# 9_Fans_Control.net
KiCad netlist of a schematic drawn in Altium Designer
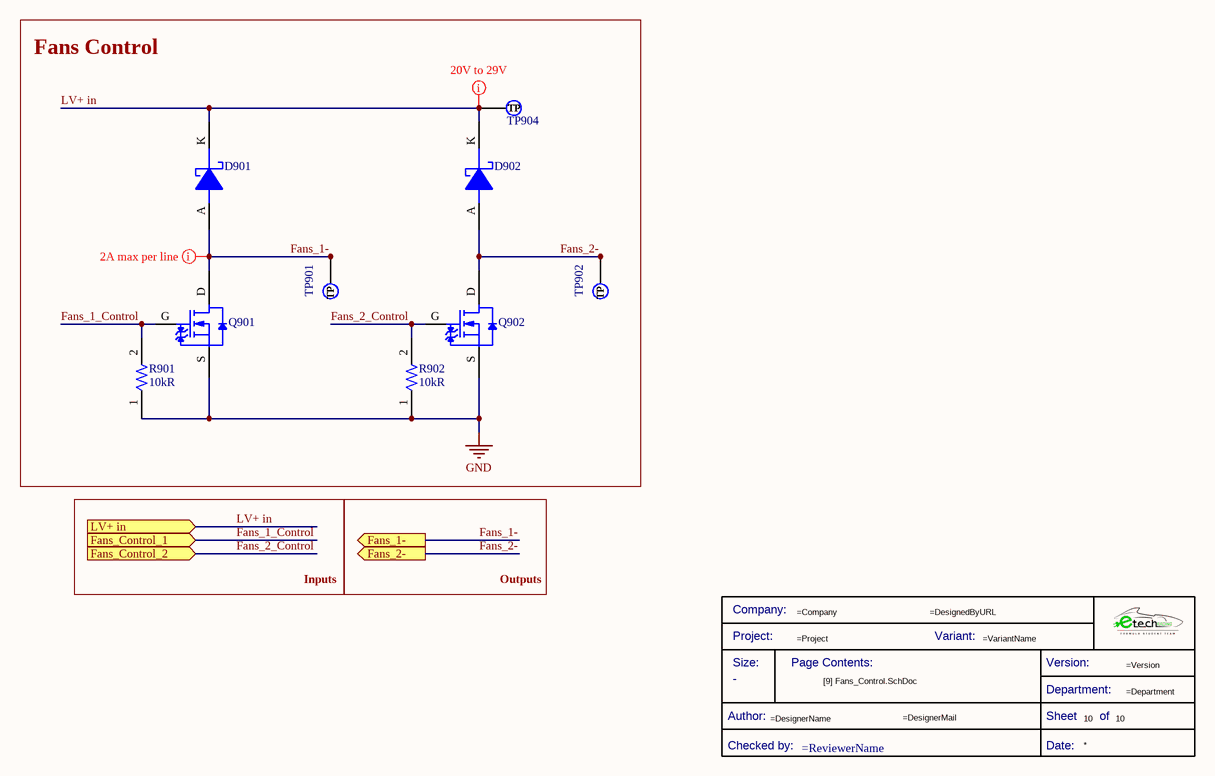
[diagram p0: [9] Fans_Control.SchDoc]

(export (version "E")
  (design (tool "Eeschema 10.0.6"))
  (components
    (comp (ref "*")
      (value "Title Block_template")
      (description "Standard Title Block")
      (fields (field (name "SIZE") "-"))
      (libsource (lib "e-Tech_Racing") (part "Title Block_template"))
    )
    (comp (ref "D901")
      (value "MBR0530")
      (footprint "DSC-SOD123")
      (description "VR=30V IF=500mA 30pF P=410mW")
      (fields (field (name ".CREATOR") "GP"))
      (libsource (lib "Filter components") (part "DSC-0.5/30-SOD123"))
    )
    (comp (ref "D902")
      (value "MBR0530")
      (footprint "DSC-SOD123")
      (description "VR=30V IF=500mA 30pF P=410mW")
      (fields (field (name ".CREATOR") "GP"))
      (libsource (lib "Filter components") (part "DSC-0.5/30-SOD123"))
    )
    (comp (ref "Q901")
      (value "CPH3455-TL-H")
      (footprint "TRT-NCH-3/35-CPH")
      (description "CPH3455-TL-H N-channel MOSFET Transistor; 3 A; 35 V; 3-Pin CPH")
      (fields (field (name "MANUFACTURER") "ON Semiconductor") (field (name ".CREATOR") "GP"))
      (libsource (lib "Semiconductor") (part "TRT-NCH-3/35-CPH"))
    )
    (comp (ref "Q902")
      (value "CPH3455-TL-H")
      (footprint "TRT-NCH-3/35-CPH")
      (description "CPH3455-TL-H N-channel MOSFET Transistor; 3 A; 35 V; 3-Pin CPH")
      (fields (field (name "MANUFACTURER") "ON Semiconductor") (field (name ".CREATOR") "GP"))
      (libsource (lib "Semiconductor") (part "TRT-NCH-3/35-CPH"))
    )
    (comp (ref "R901")
      (value "CR0805-JW-103ELF")
      (footprint "R0805FTK")
      (fields
        (field (name "TOLERANCE") "5%")
        (field (name "RESISTANCE") "10kR")
        (field (name ".CREATOR") "DR")
      )
      (libsource (lib "Passives") (part "R10k-0805FTK"))
    )
    (comp (ref "R902")
      (value "CR0805-JW-103ELF")
      (footprint "R0805FTK")
      (fields
        (field (name "TOLERANCE") "5%")
        (field (name "RESISTANCE") "10kR")
        (field (name ".CREATOR") "DR")
      )
      (libsource (lib "Passives") (part "R10k-0805FTK"))
    )
    (comp (ref "TP901")
      (value "TestPoint")
      (footprint "TestPoint")
      (description "Test Point 1x1 mm")
      (fields (field (name ".CREATOR") "GP") (field (name ".PCBCHECK") "GP") (field (name ".SCHCHECK") "GP"))
      (libsource (lib "e-Tech_Racing") (part "TestPoint"))
    )
    (comp (ref "TP902")
      (value "TestPoint")
      (footprint "TestPoint")
      (description "Test Point 1x1 mm")
      (fields (field (name ".CREATOR") "GP") (field (name ".PCBCHECK") "GP") (field (name ".SCHCHECK") "GP"))
      (libsource (lib "e-Tech_Racing") (part "TestPoint"))
    )
    (comp (ref "TP904")
      (value "TestPoint")
      (footprint "TestPoint")
      (description "Test Point 1x1 mm")
      (fields (field (name ".CREATOR") "GP") (field (name ".PCBCHECK") "GP") (field (name ".SCHCHECK") "GP"))
      (libsource (lib "e-Tech_Racing") (part "TestPoint"))
    )
  )
  (nets
    (net (code "1") (name "/Fans_1-") (class "Default")
      (node (ref "D901") (pin "A") (pinfunction "A_A") (pintype "passive"))
      (node (ref "Q901") (pin "D") (pinfunction "D_D") (pintype "passive"))
      (node (ref "TP901") (pin "1") (pinfunction "TP_1") (pintype "passive"))
    )
    (net (code "2") (name "/Fans_1_Control") (class "Default")
      (node (ref "Q901") (pin "G") (pinfunction "G_G") (pintype "passive"))
      (node (ref "R901") (pin "2") (pinfunction "2_2") (pintype "passive"))
    )
    (net (code "3") (name "/Fans_2-") (class "Default")
      (node (ref "D902") (pin "A") (pinfunction "A_A") (pintype "passive"))
      (node (ref "Q902") (pin "D") (pinfunction "D_D") (pintype "passive"))
      (node (ref "TP902") (pin "1") (pinfunction "TP_1") (pintype "passive"))
    )
    (net (code "4") (name "/Fans_2_Control") (class "Default")
      (node (ref "Q902") (pin "G") (pinfunction "G_G") (pintype "passive"))
      (node (ref "R902") (pin "2") (pinfunction "2_2") (pintype "passive"))
    )
    (net (code "5") (name "/LV+ in") (class "Default")
      (node (ref "D901") (pin "K") (pinfunction "K_K") (pintype "passive"))
      (node (ref "D902") (pin "K") (pinfunction "K_K") (pintype "passive"))
      (node (ref "TP904") (pin "1") (pinfunction "TP_1") (pintype "passive"))
    )
    (net (code "6") (name "GND") (class "Default")
      (node (ref "Q901") (pin "S") (pinfunction "S_S") (pintype "passive"))
      (node (ref "Q902") (pin "S") (pinfunction "S_S") (pintype "passive"))
      (node (ref "R901") (pin "1") (pinfunction "1_1") (pintype "passive"))
      (node (ref "R902") (pin "1") (pinfunction "1_1") (pintype "passive"))
    )
  )
)
